# dennisquad.net
KiCad netlist of a schematic drawn in EAGLE
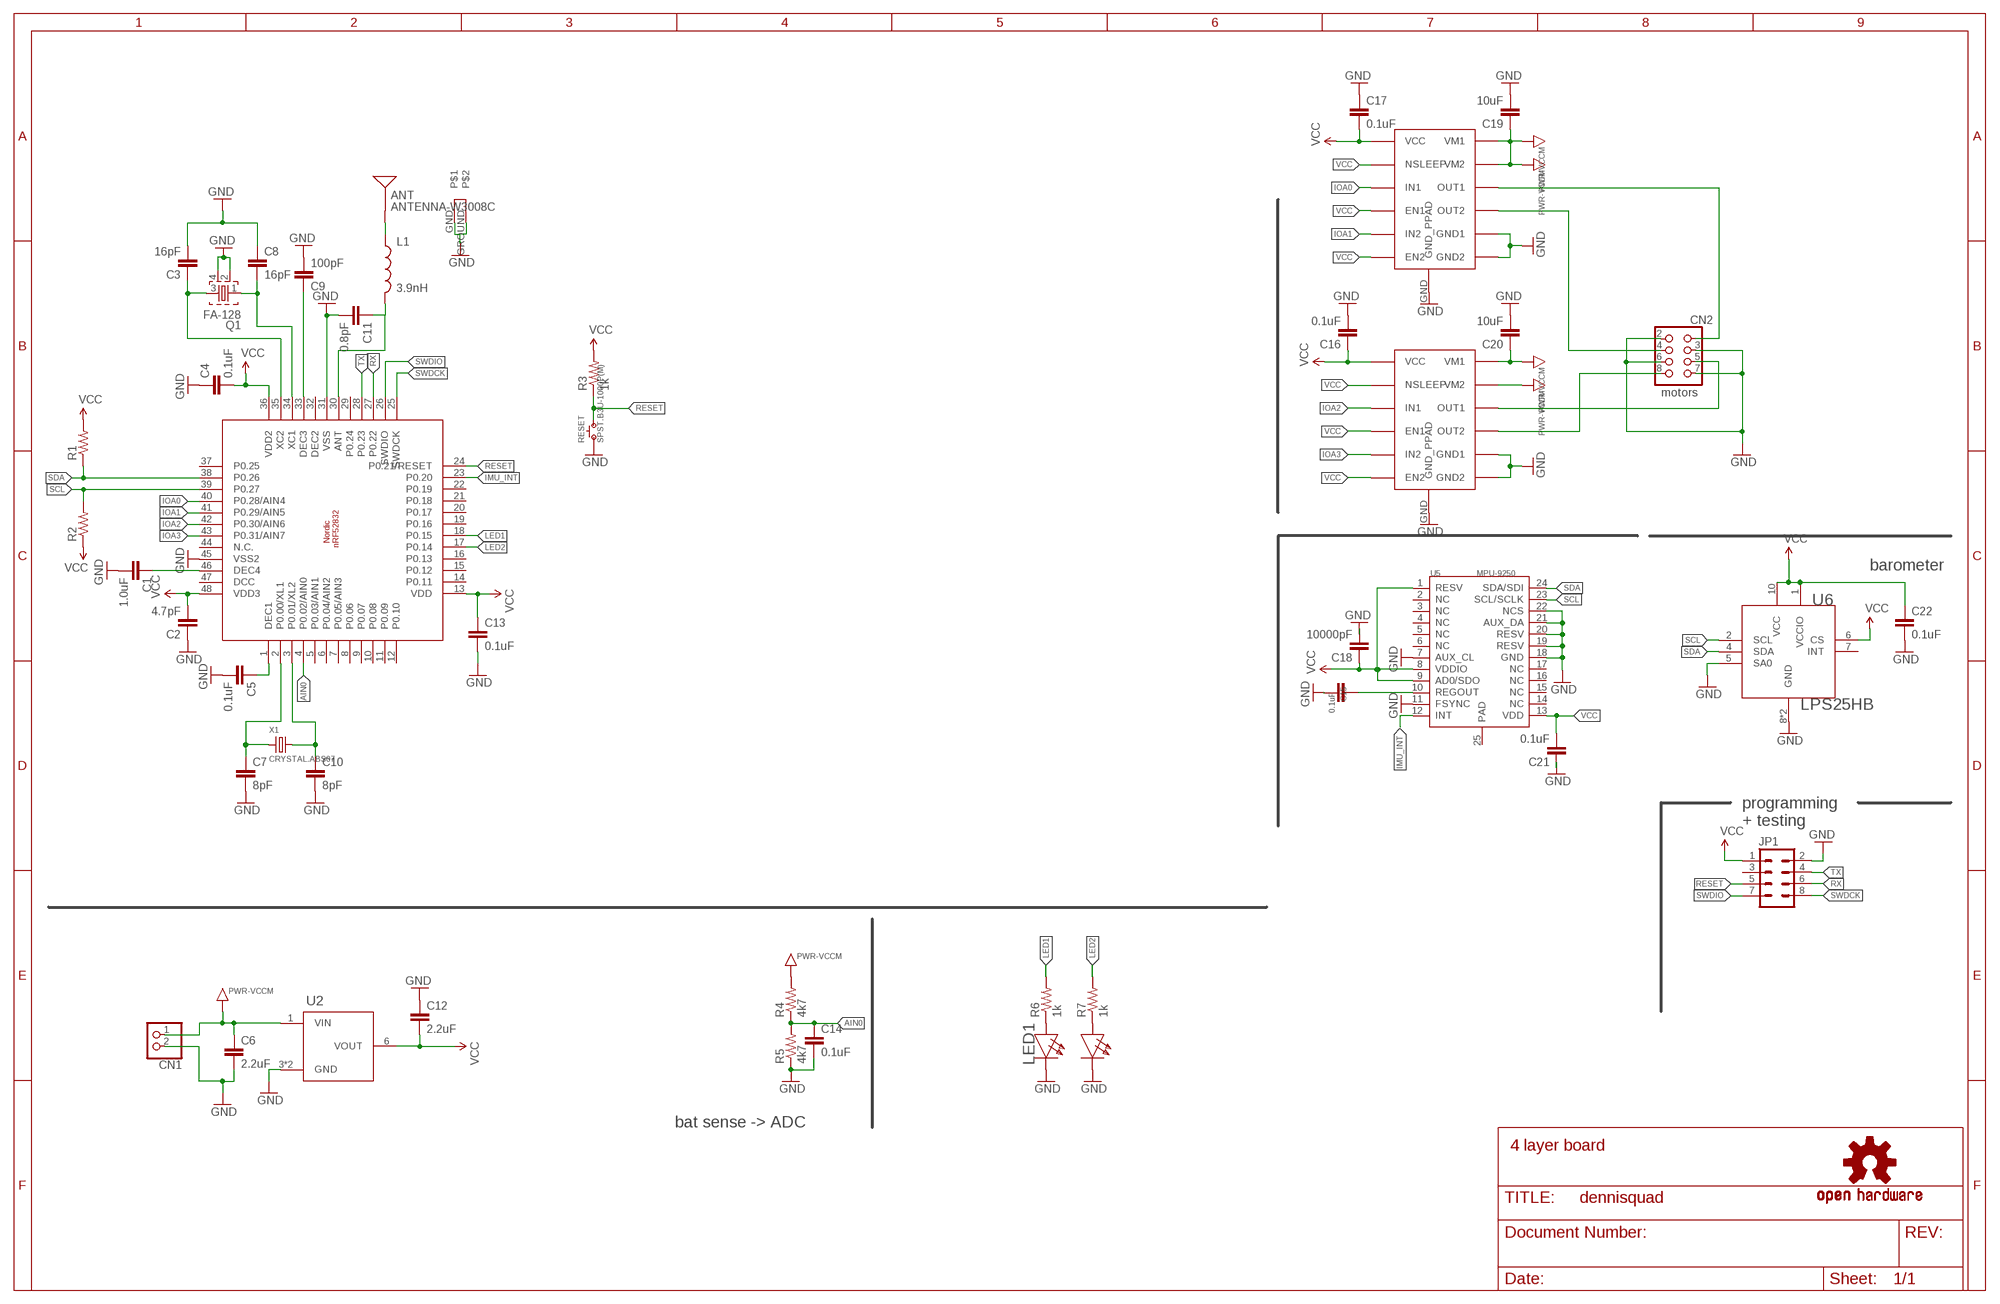
[diagram p0: schematic, sheet 1]

(export (version "E")
  (design (tool "Eeschema 10.0.6"))
  (components
    (comp (ref "ANT")
      (value "ANTENNA-W3008C")
      (footprint "eagle-import:ANTENNA-W3008C")
      (libsource (lib "eagle-import") (part "ANTENNA-W3008C"))
    )
    (comp (ref "C1")
      (value "1.0uF")
      (footprint "eagle-import:0603-CAP")
      (libsource (lib "eagle-import") (part "CAP0603-CAP"))
    )
    (comp (ref "C2")
      (value "4.7pF")
      (footprint "eagle-import:0603-CAP")
      (libsource (lib "eagle-import") (part "CAP0603-CAP"))
    )
    (comp (ref "C3")
      (value "16pF")
      (footprint "eagle-import:0402-CAP")
      (fields (field (name "MPN") "GRM1555C1H160GA01D"))
      (libsource (lib "eagle-import") (part "CAP0402-CAP"))
    )
    (comp (ref "C4")
      (value "0.1uF")
      (footprint "eagle-import:0402-CAP")
      (fields (field (name "MPN") "CL05B104JO5NNNC"))
      (libsource (lib "eagle-import") (part "CAP0402-CAP"))
    )
    (comp (ref "C5")
      (value "0.1uF")
      (footprint "eagle-import:0402-CAP")
      (fields (field (name "MPN") "CL05B104JO5NNNC"))
      (libsource (lib "eagle-import") (part "CAP0402-CAP"))
    )
    (comp (ref "C6")
      (value "2.2uF")
      (footprint "eagle-import:0402-CAP")
      (fields (field (name "MPN") "GRT155R61C225KE13D"))
      (libsource (lib "eagle-import") (part "CAP0402-CAP"))
    )
    (comp (ref "C7")
      (value "8pF")
      (footprint "eagle-import:0402-CAP")
      (fields (field (name "MPN") "GRM1555C1H8R0BA01D"))
      (libsource (lib "eagle-import") (part "CAP0402-CAP"))
    )
    (comp (ref "C8")
      (value "16pF")
      (footprint "eagle-import:0402-CAP")
      (fields (field (name "MPN") "GRM1555C1H160GA01D"))
      (libsource (lib "eagle-import") (part "CAP0402-CAP"))
    )
    (comp (ref "C9")
      (value "100pF")
      (footprint "eagle-import:0402-CAP")
      (fields (field (name "MPN") "GRM1555C1H101JA01D"))
      (libsource (lib "eagle-import") (part "CAP0402-CAP"))
    )
    (comp (ref "C10")
      (value "8pF")
      (footprint "eagle-import:0402-CAP")
      (fields (field (name "MPN") "GRM1555C1H8R0BA01D"))
      (libsource (lib "eagle-import") (part "CAP0402-CAP"))
    )
    (comp (ref "C11")
      (value "0.8pF")
      (footprint "eagle-import:0402-CAP")
      (fields (field (name "MPN") "GRM1555C2AR80BA01D"))
      (libsource (lib "eagle-import") (part "CAP0402-CAP"))
    )
    (comp (ref "C12")
      (value "2.2uF")
      (footprint "eagle-import:0402-CAP")
      (fields (field (name "MPN") "GRT155R61C225KE13D"))
      (libsource (lib "eagle-import") (part "CAP0402-CAP"))
    )
    (comp (ref "C13")
      (value "0.1uF")
      (footprint "eagle-import:0402-CAP")
      (fields (field (name "MPN") "CL05B104JO5NNNC"))
      (libsource (lib "eagle-import") (part "CAP0402-CAP"))
    )
    (comp (ref "C14")
      (value "0.1uF")
      (footprint "eagle-import:0402-CAP")
      (fields (field (name "MPN") "CL05B104JO5NNNC"))
      (libsource (lib "eagle-import") (part "CAP0402-CAP"))
    )
    (comp (ref "C15")
      (value "0.1uF")
      (footprint "eagle-import:0402-CAP")
      (fields (field (name "MPN") "CL05B104JO5NNNC"))
      (libsource (lib "eagle-import") (part "CAP0402-CAP"))
    )
    (comp (ref "C16")
      (value "0.1uF")
      (footprint "eagle-import:0402-CAP")
      (fields (field (name "MPN") "CL05B104JO5NNNC"))
      (libsource (lib "eagle-import") (part "CAP0402-CAP"))
    )
    (comp (ref "C17")
      (value "0.1uF")
      (footprint "eagle-import:0402-CAP")
      (fields (field (name "MPN") "CL05B104JO5NNNC"))
      (libsource (lib "eagle-import") (part "CAP0402-CAP"))
    )
    (comp (ref "C18")
      (value "10000pF")
      (footprint "eagle-import:0402-CAP")
      (fields (field (name "MPN") "CL05B103KP5NNNC"))
      (libsource (lib "eagle-import") (part "CAP0402-CAP"))
    )
    (comp (ref "C19")
      (value "10uF")
      (footprint "eagle-import:0603-CAP")
      (fields (field (name "MPN") "C1206C106M4RACAUTO"))
      (libsource (lib "eagle-import") (part "CAP0603-CAP"))
    )
    (comp (ref "C20")
      (value "10uF")
      (footprint "eagle-import:0603-CAP")
      (fields (field (name "MPN") "C1206C106M4RACAUTO"))
      (libsource (lib "eagle-import") (part "CAP0603-CAP"))
    )
    (comp (ref "C21")
      (value "0.1uF")
      (footprint "eagle-import:0402-CAP")
      (fields (field (name "MPN") "CL05B104JO5NNNC"))
      (libsource (lib "eagle-import") (part "CAP0402-CAP"))
    )
    (comp (ref "C22")
      (value "0.1uF")
      (footprint "eagle-import:0402-CAP")
      (fields (field (name "MPN") "CL05B104JO5NNNC"))
      (libsource (lib "eagle-import") (part "CAP0402-CAP"))
    )
    (comp (ref "CN1")
      (value "JST_2PIN-THM")
      (footprint "eagle-import:JST-PH-2-THM")
      (libsource (lib "eagle-import") (part "JST_2PIN-THM"))
    )
    (comp (ref "CN2")
      (value "HEADER-2X4")
      (footprint "eagle-import:HEADER-2X04-THM")
      (libsource (lib "eagle-import") (part "HEADER-2X4"))
    )
    (comp (ref "JP1")
      (value "M04X2")
      (footprint "eagle-import:2X4")
      (libsource (lib "eagle-import") (part "M04X2"))
    )
    (comp (ref "L1")
      (value "3.9nH")
      (footprint "eagle-import:0603")
      (fields (field (name "MPN") "AISC-0402-3N9J-T"))
      (libsource (lib "eagle-import") (part "INDUCTOR0603"))
    )
    (comp (ref "LED1")
      (value "LED-DUAL0805")
      (footprint "eagle-import:SMD0805-DUAL")
      (fields (field (name "MPN") "APHBM2012QBDSURKC"))
      (libsource (lib "eagle-import") (part "LED-DUAL0805"))
    )
    (comp (ref "LOGO1")
      (value "OSHW-LOGOM")
      (footprint "eagle-import:OSHW-LOGO-M")
      (libsource (lib "eagle-import") (part "OSHW-LOGOM"))
    )
    (comp (ref "Q1")
      (value "FA-128")
      (footprint "eagle-import:FA-128")
      (fields (field (name "MPN") "FA-128 32.0000MF20X-K3"))
      (libsource (lib "eagle-import") (part "FA-128"))
    )
    (comp (ref "R1")
      (value "RESISTOR0402")
      (footprint "eagle-import:0402-RES")
      (libsource (lib "eagle-import") (part "RESISTOR0402"))
    )
    (comp (ref "R2")
      (value "RESISTOR0402")
      (footprint "eagle-import:0402-RES")
      (libsource (lib "eagle-import") (part "RESISTOR0402"))
    )
    (comp (ref "R3")
      (value "1k")
      (footprint "eagle-import:0402-RES")
      (fields (field (name "MPN") "ERJ-2GEJ102X"))
      (libsource (lib "eagle-import") (part "RESISTOR0402"))
    )
    (comp (ref "R4")
      (value "4k7")
      (footprint "eagle-import:0402-RES")
      (fields (field (name "MPN") "ERJ-PA2F4701X"))
      (libsource (lib "eagle-import") (part "RESISTOR0402"))
    )
    (comp (ref "R5")
      (value "4k7")
      (footprint "eagle-import:0402-RES")
      (fields (field (name "MPN") "ERJ-PA2F4701X"))
      (libsource (lib "eagle-import") (part "RESISTOR0402"))
    )
    (comp (ref "R6")
      (value "1k")
      (footprint "eagle-import:0402-RES")
      (fields (field (name "MPN") "ERJ-2GEJ102X"))
      (libsource (lib "eagle-import") (part "RESISTOR0402"))
    )
    (comp (ref "R7")
      (value "1k")
      (footprint "eagle-import:0402-RES")
      (fields (field (name "MPN") "ERJ-2GEJ102X"))
      (libsource (lib "eagle-import") (part "RESISTOR0402"))
    )
    (comp (ref "RESET")
      (value "SPST.B3U-1000P(M)")
      (footprint "eagle-import:B3U-1000P(M)")
      (libsource (lib "eagle-import") (part "SPST.B3U-1000P(M)"))
    )
    (comp (ref "U1")
      (value "NRF52832_QFN48")
      (footprint "eagle-import:QFN48")
      (libsource (lib "eagle-import") (part "NRF52832_QFN48"))
    )
    (comp (ref "U2")
      (value "MCP1700T-3302E/MAY")
      (footprint "eagle-import:6-VDFN")
      (libsource (lib "eagle-import") (part "MCP1700T-3302E/MAY"))
    )
    (comp (ref "U3")
      (value "DRV8839")
      (footprint "eagle-import:PWSON-N12")
      (libsource (lib "eagle-import") (part "DRV8839"))
    )
    (comp (ref "U4")
      (value "DRV8839")
      (footprint "eagle-import:PWSON-N12")
      (libsource (lib "eagle-import") (part "DRV8839"))
    )
    (comp (ref "U5")
      (value "MPU-9250")
      (footprint "eagle-import:LEAD-QFN24")
      (libsource (lib "eagle-import") (part "MPU-9250"))
    )
    (comp (ref "U6")
      (value "LPS25HB")
      (footprint "eagle-import:HLGA10L")
      (libsource (lib "eagle-import") (part "LPS25HB"))
    )
    (comp (ref "X1")
      (value "CRYSTAL.ABS07")
      (footprint "eagle-import:ABS07")
      (fields (field (name "MPN") "ABS07-120-32.768KHZ-T"))
      (libsource (lib "eagle-import") (part "CRYSTAL.ABS07"))
    )
  )
  (nets
    (net (code "1") (name "/DCC") (class "Default")
      (node (ref "U1") (pin "47") (pinfunction "DCC_47") (pintype "power_in"))
    )
    (net (code "2") (name "/DEC2") (class "Default")
      (node (ref "U1") (pin "32") (pinfunction "DEC2_32") (pintype "power_in"))
    )
    (net (code "3") (name "AIN0") (class "Default")
      (node (ref "C14") (pin "1") (pinfunction "1_1") (pintype "passive"))
      (node (ref "R4") (pin "1") (pinfunction "1_1") (pintype "passive"))
      (node (ref "R5") (pin "2") (pinfunction "2_2") (pintype "passive"))
      (node (ref "U1") (pin "4") (pinfunction "P0.02/AIN0_4") (pintype "bidirectional"))
    )
    (net (code "4") (name "GND") (class "Default")
      (node (ref "ANT") (pin "GND") (pinfunction "P$1_GND") (pintype "bidirectional"))
      (node (ref "ANT") (pin "GROUND") (pinfunction "P$2_GROUND") (pintype "bidirectional"))
      (node (ref "C1") (pin "2") (pinfunction "2_2") (pintype "passive"))
      (node (ref "C10") (pin "2") (pinfunction "2_2") (pintype "passive"))
      (node (ref "C11") (pin "2") (pinfunction "2_2") (pintype "passive"))
      (node (ref "C12") (pin "1") (pinfunction "1_1") (pintype "passive"))
      (node (ref "C13") (pin "2") (pinfunction "2_2") (pintype "passive"))
      (node (ref "C14") (pin "2") (pinfunction "2_2") (pintype "passive"))
      (node (ref "C15") (pin "2") (pinfunction "2_2") (pintype "passive"))
      (node (ref "C16") (pin "2") (pinfunction "2_2") (pintype "passive"))
      (node (ref "C17") (pin "1") (pinfunction "1_1") (pintype "passive"))
      (node (ref "C18") (pin "2") (pinfunction "2_2") (pintype "passive"))
      (node (ref "C19") (pin "2") (pinfunction "2_2") (pintype "passive"))
      (node (ref "C2") (pin "1") (pinfunction "1_1") (pintype "passive"))
      (node (ref "C20") (pin "2") (pinfunction "2_2") (pintype "passive"))
      (node (ref "C21") (pin "1") (pinfunction "1_1") (pintype "passive"))
      (node (ref "C22") (pin "2") (pinfunction "2_2") (pintype "passive"))
      (node (ref "C3") (pin "2") (pinfunction "2_2") (pintype "passive"))
      (node (ref "C4") (pin "1") (pinfunction "1_1") (pintype "passive"))
      (node (ref "C5") (pin "2") (pinfunction "2_2") (pintype "passive"))
      (node (ref "C6") (pin "2") (pinfunction "2_2") (pintype "passive"))
      (node (ref "C7") (pin "2") (pinfunction "2_2") (pintype "passive"))
      (node (ref "C8") (pin "1") (pinfunction "1_1") (pintype "passive"))
      (node (ref "C9") (pin "2") (pinfunction "2_2") (pintype "passive"))
      (node (ref "CN1") (pin "2") (pinfunction "1_2") (pintype "passive"))
      (node (ref "CN2") (pin "2") (pinfunction "P$2_2") (pintype "passive"))
      (node (ref "CN2") (pin "3") (pinfunction "P$3_3") (pintype "passive"))
      (node (ref "CN2") (pin "6") (pinfunction "P$6_6") (pintype "passive"))
      (node (ref "CN2") (pin "7") (pinfunction "P$7_7") (pintype "passive"))
      (node (ref "JP1") (pin "2") (pinfunction "2_2") (pintype "passive"))
      (node (ref "LED1") (pin "2") (pinfunction "CB_2") (pintype "passive"))
      (node (ref "LED1") (pin "3") (pinfunction "CR_3") (pintype "passive"))
      (node (ref "Q1") (pin "2") (pinfunction "2_2") (pintype "passive"))
      (node (ref "Q1") (pin "4") (pinfunction "4_4") (pintype "passive"))
      (node (ref "R5") (pin "1") (pinfunction "1_1") (pintype "passive"))
      (node (ref "RESET") (pin "1") (pinfunction "1_1") (pintype "bidirectional"))
      (node (ref "U1") (pin "31") (pinfunction "VSS_31") (pintype "power_in"))
      (node (ref "U1") (pin "45") (pinfunction "VSS2_45") (pintype "power_in"))
      (node (ref "U2") (pin "3") (pinfunction "GND_3") (pintype "bidirectional"))
      (node (ref "U2") (pin "P$1") (pinfunction "GND_P$1") (pintype "bidirectional"))
      (node (ref "U3") (pin "GND") (pinfunction "GND_PPAD_GND") (pintype "bidirectional"))
      (node (ref "U3") (pin "P$5") (pinfunction "GND1_P$5") (pintype "bidirectional"))
      (node (ref "U3") (pin "P$6") (pinfunction "GND2_P$6") (pintype "bidirectional"))
      (node (ref "U4") (pin "GND") (pinfunction "GND_PPAD_GND") (pintype "bidirectional"))
      (node (ref "U4") (pin "P$5") (pinfunction "GND1_P$5") (pintype "bidirectional"))
      (node (ref "U4") (pin "P$6") (pinfunction "GND2_P$6") (pintype "bidirectional"))
      (node (ref "U5") (pin "11") (pinfunction "FSYNC_11") (pintype "bidirectional"))
      (node (ref "U5") (pin "18") (pinfunction "GND_18") (pintype "bidirectional"))
      (node (ref "U5") (pin "19") (pinfunction "RESV_19") (pintype "bidirectional"))
      (node (ref "U5") (pin "20") (pinfunction "RESV_20") (pintype "bidirectional"))
      (node (ref "U5") (pin "21") (pinfunction "AUX_DA_21") (pintype "bidirectional"))
      (node (ref "U5") (pin "22") (pinfunction "NCS_22") (pintype "bidirectional"))
      (node (ref "U5") (pin "7") (pinfunction "AUX_CL_7") (pintype "bidirectional"))
      (node (ref "U6") (pin "5") (pinfunction "SA0_5") (pintype "bidirectional"))
      (node (ref "U6") (pin "8") (pinfunction "GND_8") (pintype "bidirectional"))
      (node (ref "U6") (pin "9") (pinfunction "GND_9") (pintype "bidirectional"))
    )
    (net (code "5") (name "IMU_INT") (class "Default")
      (node (ref "U1") (pin "23") (pinfunction "P0.20_23") (pintype "bidirectional"))
      (node (ref "U5") (pin "12") (pinfunction "INT_12") (pintype "bidirectional"))
    )
    (net (code "6") (name "IOA0") (class "Default")
      (node (ref "U1") (pin "40") (pinfunction "P0.28/AIN4_40") (pintype "bidirectional"))
      (node (ref "U3") (pin "P$9") (pinfunction "IN1_P$9") (pintype "bidirectional"))
    )
    (net (code "7") (name "IOA1") (class "Default")
      (node (ref "U1") (pin "41") (pinfunction "P0.29/AIN5_41") (pintype "bidirectional"))
      (node (ref "U3") (pin "P$11") (pinfunction "IN2_P$11") (pintype "bidirectional"))
    )
    (net (code "8") (name "IOA2") (class "Default")
      (node (ref "U1") (pin "42") (pinfunction "P0.30/AIN6_42") (pintype "bidirectional"))
      (node (ref "U4") (pin "P$9") (pinfunction "IN1_P$9") (pintype "bidirectional"))
    )
    (net (code "9") (name "IOA3") (class "Default")
      (node (ref "U1") (pin "43") (pinfunction "P0.31/AIN7_43") (pintype "bidirectional"))
      (node (ref "U4") (pin "P$11") (pinfunction "IN2_P$11") (pintype "bidirectional"))
    )
    (net (code "10") (name "LED1") (class "Default")
      (node (ref "R6") (pin "2") (pinfunction "2_2") (pintype "passive"))
      (node (ref "U1") (pin "18") (pinfunction "P0.15_18") (pintype "bidirectional"))
    )
    (net (code "11") (name "LED2") (class "Default")
      (node (ref "R7") (pin "2") (pinfunction "2_2") (pintype "passive"))
      (node (ref "U1") (pin "17") (pinfunction "P0.14_17") (pintype "bidirectional"))
    )
    (net (code "12") (name "Net-(ANT-SIGNAL)") (class "Default")
      (node (ref "ANT") (pin "FEED") (pinfunction "SIGNAL_FEED") (pintype "bidirectional"))
      (node (ref "L1") (pin "1") (pinfunction "1_1") (pintype "passive"))
    )
    (net (code "13") (name "Net-(CN2-P$1)") (class "Default")
      (node (ref "CN2") (pin "1") (pinfunction "P$1_1") (pintype "passive"))
      (node (ref "U3") (pin "P$3") (pinfunction "OUT1_P$3") (pintype "bidirectional"))
    )
    (net (code "14") (name "Net-(CN2-P$4)") (class "Default")
      (node (ref "CN2") (pin "4") (pinfunction "P$4_4") (pintype "passive"))
      (node (ref "U3") (pin "P$4") (pinfunction "OUT2_P$4") (pintype "bidirectional"))
    )
    (net (code "15") (name "Net-(CN2-P$5)") (class "Default")
      (node (ref "CN2") (pin "5") (pinfunction "P$5_5") (pintype "passive"))
      (node (ref "U4") (pin "P$3") (pinfunction "OUT1_P$3") (pintype "bidirectional"))
    )
    (net (code "16") (name "Net-(CN2-P$8)") (class "Default")
      (node (ref "CN2") (pin "8") (pinfunction "P$8_8") (pintype "passive"))
      (node (ref "U4") (pin "P$4") (pinfunction "OUT2_P$4") (pintype "bidirectional"))
    )
    (net (code "17") (name "Net-(LED1-AB)") (class "Default")
      (node (ref "LED1") (pin "1") (pinfunction "AB_1") (pintype "passive"))
      (node (ref "R6") (pin "1") (pinfunction "1_1") (pintype "passive"))
    )
    (net (code "18") (name "Net-(LED1-AR)") (class "Default")
      (node (ref "LED1") (pin "4") (pinfunction "AR_4") (pintype "passive"))
      (node (ref "R7") (pin "1") (pinfunction "1_1") (pintype "passive"))
    )
    (net (code "19") (name "Net-(U1-ANT)") (class "Default")
      (node (ref "C11") (pin "1") (pinfunction "1_1") (pintype "passive"))
      (node (ref "L1") (pin "2") (pinfunction "2_2") (pintype "passive"))
      (node (ref "U1") (pin "30") (pinfunction "ANT_30") (pintype "bidirectional"))
    )
    (net (code "20") (name "Net-(U1-DEC1)") (class "Default")
      (node (ref "C5") (pin "1") (pinfunction "1_1") (pintype "passive"))
      (node (ref "U1") (pin "1") (pinfunction "DEC1_1") (pintype "power_in"))
    )
    (net (code "21") (name "Net-(U1-DEC3)") (class "Default")
      (node (ref "C9") (pin "1") (pinfunction "1_1") (pintype "passive"))
      (node (ref "U1") (pin "33") (pinfunction "DEC3_33") (pintype "power_in"))
    )
    (net (code "22") (name "Net-(U1-DEC4)") (class "Default")
      (node (ref "C1") (pin "1") (pinfunction "1_1") (pintype "passive"))
      (node (ref "U1") (pin "46") (pinfunction "DEC4_46") (pintype "bidirectional"))
    )
    (net (code "23") (name "Net-(U1-P0.00{slash}XL1)") (class "Default")
      (node (ref "C7") (pin "1") (pinfunction "1_1") (pintype "passive"))
      (node (ref "U1") (pin "2") (pinfunction "P0.00/XL1_2") (pintype "bidirectional"))
      (node (ref "X1") (pin "1") (pinfunction "1_1") (pintype "passive"))
    )
    (net (code "24") (name "Net-(U1-P0.01{slash}XL2)") (class "Default")
      (node (ref "C10") (pin "1") (pinfunction "1_1") (pintype "passive"))
      (node (ref "U1") (pin "3") (pinfunction "P0.01/XL2_3") (pintype "bidirectional"))
      (node (ref "X1") (pin "2") (pinfunction "2_2") (pintype "passive"))
    )
    (net (code "25") (name "Net-(U1-XC1)") (class "Default")
      (node (ref "C8") (pin "2") (pinfunction "2_2") (pintype "passive"))
      (node (ref "Q1") (pin "1") (pinfunction "1_1") (pintype "passive"))
      (node (ref "U1") (pin "34") (pinfunction "XC1_34") (pintype "bidirectional"))
    )
    (net (code "26") (name "Net-(U1-XC2)") (class "Default")
      (node (ref "C3") (pin "1") (pinfunction "1_1") (pintype "passive"))
      (node (ref "Q1") (pin "3") (pinfunction "3_3") (pintype "passive"))
      (node (ref "U1") (pin "35") (pinfunction "XC2_35") (pintype "bidirectional"))
    )
    (net (code "27") (name "Net-(U5-REGOUT)") (class "Default")
      (node (ref "C15") (pin "1") (pinfunction "1_1") (pintype "passive"))
      (node (ref "U5") (pin "10") (pinfunction "REGOUT_10") (pintype "bidirectional"))
    )
    (net (code "28") (name "PWR-VCCM") (class "Default")
      (node (ref "C19") (pin "1") (pinfunction "1_1") (pintype "passive"))
      (node (ref "C20") (pin "1") (pinfunction "1_1") (pintype "passive"))
      (node (ref "C6") (pin "1") (pinfunction "1_1") (pintype "passive"))
      (node (ref "CN1") (pin "1") (pinfunction "2_1") (pintype "passive"))
      (node (ref "R4") (pin "2") (pinfunction "2_2") (pintype "passive"))
      (node (ref "U2") (pin "1") (pinfunction "VIN_1") (pintype "bidirectional"))
      (node (ref "U3") (pin "P$1") (pinfunction "VM1_P$1") (pintype "bidirectional"))
      (node (ref "U3") (pin "P$2") (pinfunction "VM2_P$2") (pintype "bidirectional"))
      (node (ref "U4") (pin "P$1") (pinfunction "VM1_P$1") (pintype "bidirectional"))
      (node (ref "U4") (pin "P$2") (pinfunction "VM2_P$2") (pintype "bidirectional"))
    )
    (net (code "29") (name "RESET") (class "Default")
      (node (ref "JP1") (pin "5") (pinfunction "5_5") (pintype "passive"))
      (node (ref "R3") (pin "1") (pinfunction "1_1") (pintype "passive"))
      (node (ref "RESET") (pin "2") (pinfunction "2_2") (pintype "bidirectional"))
      (node (ref "U1") (pin "24") (pinfunction "P0.21/RESET_24") (pintype "bidirectional"))
    )
    (net (code "30") (name "RX") (class "Default")
      (node (ref "JP1") (pin "6") (pinfunction "6_6") (pintype "passive"))
      (node (ref "U1") (pin "27") (pinfunction "P0.22_27") (pintype "bidirectional"))
    )
    (net (code "31") (name "SCL") (class "Default")
      (node (ref "R2") (pin "2") (pinfunction "2_2") (pintype "passive"))
      (node (ref "U1") (pin "39") (pinfunction "P0.27_39") (pintype "bidirectional"))
      (node (ref "U5") (pin "23") (pinfunction "SCL/SCLK_23") (pintype "bidirectional"))
      (node (ref "U6") (pin "2") (pinfunction "SCL_2") (pintype "bidirectional"))
    )
    (net (code "32") (name "SDA") (class "Default")
      (node (ref "R1") (pin "1") (pinfunction "1_1") (pintype "passive"))
      (node (ref "U1") (pin "38") (pinfunction "P0.26_38") (pintype "bidirectional"))
      (node (ref "U5") (pin "24") (pinfunction "SDA/SDI_24") (pintype "bidirectional"))
      (node (ref "U6") (pin "4") (pinfunction "SDA_4") (pintype "bidirectional"))
    )
    (net (code "33") (name "SWDCK") (class "Default")
      (node (ref "JP1") (pin "8") (pinfunction "8_8") (pintype "passive"))
      (node (ref "U1") (pin "25") (pinfunction "SWDCK_25") (pintype "open_collector"))
    )
    (net (code "34") (name "SWDIO") (class "Default")
      (node (ref "JP1") (pin "7") (pinfunction "7_7") (pintype "passive"))
      (node (ref "U1") (pin "26") (pinfunction "SWDIO_26") (pintype "bidirectional"))
    )
    (net (code "35") (name "TX") (class "Default")
      (node (ref "JP1") (pin "4") (pinfunction "4_4") (pintype "passive"))
      (node (ref "U1") (pin "28") (pinfunction "P0.23_28") (pintype "bidirectional"))
    )
    (net (code "36") (name "VCC") (class "Default")
      (node (ref "C12") (pin "2") (pinfunction "2_2") (pintype "passive"))
      (node (ref "C13") (pin "1") (pinfunction "1_1") (pintype "passive"))
      (node (ref "C16") (pin "1") (pinfunction "1_1") (pintype "passive"))
      (node (ref "C17") (pin "2") (pinfunction "2_2") (pintype "passive"))
      (node (ref "C18") (pin "1") (pinfunction "1_1") (pintype "passive"))
      (node (ref "C2") (pin "2") (pinfunction "2_2") (pintype "passive"))
      (node (ref "C21") (pin "2") (pinfunction "2_2") (pintype "passive"))
      (node (ref "C22") (pin "1") (pinfunction "1_1") (pintype "passive"))
      (node (ref "C4") (pin "2") (pinfunction "2_2") (pintype "passive"))
      (node (ref "JP1") (pin "1") (pinfunction "1_1") (pintype "passive"))
      (node (ref "R1") (pin "2") (pinfunction "2_2") (pintype "passive"))
      (node (ref "R2") (pin "1") (pinfunction "1_1") (pintype "passive"))
      (node (ref "R3") (pin "2") (pinfunction "2_2") (pintype "passive"))
      (node (ref "U1") (pin "13") (pinfunction "VDD_13") (pintype "power_in"))
      (node (ref "U1") (pin "36") (pinfunction "VDD2_36") (pintype "power_in"))
      (node (ref "U1") (pin "48") (pinfunction "VDD3_48") (pintype "power_in"))
      (node (ref "U2") (pin "6") (pinfunction "VOUT_6") (pintype "bidirectional"))
      (node (ref "U3") (pin "P$10") (pinfunction "EN1_P$10") (pintype "bidirectional"))
      (node (ref "U3") (pin "P$12") (pinfunction "EN2_P$12") (pintype "bidirectional"))
      (node (ref "U3") (pin "P$7") (pinfunction "VCC_P$7") (pintype "bidirectional"))
      (node (ref "U3") (pin "P$8") (pinfunction "NSLEEP_P$8") (pintype "bidirectional"))
      (node (ref "U4") (pin "P$10") (pinfunction "EN1_P$10") (pintype "bidirectional"))
      (node (ref "U4") (pin "P$12") (pinfunction "EN2_P$12") (pintype "bidirectional"))
      (node (ref "U4") (pin "P$7") (pinfunction "VCC_P$7") (pintype "bidirectional"))
      (node (ref "U4") (pin "P$8") (pinfunction "NSLEEP_P$8") (pintype "bidirectional"))
      (node (ref "U5") (pin "1") (pinfunction "RESV_1") (pintype "bidirectional"))
      (node (ref "U5") (pin "13") (pinfunction "VDD_13") (pintype "bidirectional"))
      (node (ref "U5") (pin "8") (pinfunction "VDDIO_8") (pintype "bidirectional"))
      (node (ref "U5") (pin "9") (pinfunction "AD0/SDO_9") (pintype "bidirectional"))
      (node (ref "U6") (pin "1") (pinfunction "VCCIO_1") (pintype "bidirectional"))
      (node (ref "U6") (pin "10") (pinfunction "VCC_10") (pintype "bidirectional"))
      (node (ref "U6") (pin "6") (pinfunction "CS_6") (pintype "bidirectional"))
    )
    (net (code "37") (name "unconnected-(JP1-Pad3)") (class "Default")
      (node (ref "JP1") (pin "3") (pinfunction "3_3") (pintype "passive"))
    )
    (net (code "38") (name "unconnected-(U1-N.C.-Pad44)") (class "Default")
      (node (ref "U1") (pin "44") (pinfunction "N.C._44") (pintype "no_connect"))
    )
    (net (code "39") (name "unconnected-(U1-P0.03{slash}AIN1-Pad5)") (class "Default")
      (node (ref "U1") (pin "5") (pinfunction "P0.03/AIN1_5") (pintype "bidirectional"))
    )
    (net (code "40") (name "unconnected-(U1-P0.04{slash}AIN2-Pad6)") (class "Default")
      (node (ref "U1") (pin "6") (pinfunction "P0.04/AIN2_6") (pintype "bidirectional"))
    )
    (net (code "41") (name "unconnected-(U1-P0.05{slash}AIN3-Pad7)") (class "Default")
      (node (ref "U1") (pin "7") (pinfunction "P0.05/AIN3_7") (pintype "bidirectional"))
    )
    (net (code "42") (name "unconnected-(U1-P0.06-Pad8)") (class "Default")
      (node (ref "U1") (pin "8") (pinfunction "P0.06_8") (pintype "bidirectional"))
    )
    (net (code "43") (name "unconnected-(U1-P0.07-Pad9)") (class "Default")
      (node (ref "U1") (pin "9") (pinfunction "P0.07_9") (pintype "bidirectional"))
    )
    (net (code "44") (name "unconnected-(U1-P0.08-Pad10)") (class "Default")
      (node (ref "U1") (pin "10") (pinfunction "P0.08_10") (pintype "bidirectional"))
    )
    (net (code "45") (name "unconnected-(U1-P0.09-Pad11)") (class "Default")
      (node (ref "U1") (pin "11") (pinfunction "P0.09_11") (pintype "bidirectional"))
    )
    (net (code "46") (name "unconnected-(U1-P0.10-Pad12)") (class "Default")
      (node (ref "U1") (pin "12") (pinfunction "P0.10_12") (pintype "bidirectional"))
    )
    (net (code "47") (name "unconnected-(U1-P0.11-Pad14)") (class "Default")
      (node (ref "U1") (pin "14") (pinfunction "P0.11_14") (pintype "bidirectional"))
    )
    (net (code "48") (name "unconnected-(U1-P0.12-Pad15)") (class "Default")
      (node (ref "U1") (pin "15") (pinfunction "P0.12_15") (pintype "bidirectional"))
    )
    (net (code "49") (name "unconnected-(U1-P0.13-Pad16)") (class "Default")
      (node (ref "U1") (pin "16") (pinfunction "P0.13_16") (pintype "bidirectional"))
    )
    (net (code "50") (name "unconnected-(U1-P0.16-Pad19)") (class "Default")
      (node (ref "U1") (pin "19") (pinfunction "P0.16_19") (pintype "bidirectional"))
    )
    (net (code "51") (name "unconnected-(U1-P0.17-Pad20)") (class "Default")
      (node (ref "U1") (pin "20") (pinfunction "P0.17_20") (pintype "bidirectional"))
    )
    (net (code "52") (name "unconnected-(U1-P0.18-Pad21)") (class "Default")
      (node (ref "U1") (pin "21") (pinfunction "P0.18_21") (pintype "bidirectional"))
    )
    (net (code "53") (name "unconnected-(U1-P0.19-Pad22)") (class "Default")
      (node (ref "U1") (pin "22") (pinfunction "P0.19_22") (pintype "bidirectional"))
    )
    (net (code "54") (name "unconnected-(U1-P0.24-Pad29)") (class "Default")
      (node (ref "U1") (pin "29") (pinfunction "P0.24_29") (pintype "bidirectional"))
    )
    (net (code "55") (name "unconnected-(U1-P0.25-Pad37)") (class "Default")
      (node (ref "U1") (pin "37") (pinfunction "P0.25_37") (pintype "bidirectional"))
    )
    (net (code "56") (name "unconnected-(U5-NC-Pad2)") (class "Default")
      (node (ref "U5") (pin "2") (pinfunction "NC_2") (pintype "bidirectional"))
    )
    (net (code "57") (name "unconnected-(U5-NC-Pad3)") (class "Default")
      (node (ref "U5") (pin "3") (pinfunction "NC_3") (pintype "bidirectional"))
    )
    (net (code "58") (name "unconnected-(U5-NC-Pad4)") (class "Default")
      (node (ref "U5") (pin "4") (pinfunction "NC_4") (pintype "bidirectional"))
    )
    (net (code "59") (name "unconnected-(U5-NC-Pad5)") (class "Default")
      (node (ref "U5") (pin "5") (pinfunction "NC_5") (pintype "bidirectional"))
    )
    (net (code "60") (name "unconnected-(U5-NC-Pad6)") (class "Default")
      (node (ref "U5") (pin "6") (pinfunction "NC_6") (pintype "bidirectional"))
    )
    (net (code "61") (name "unconnected-(U5-NC-Pad14)") (class "Default")
      (node (ref "U5") (pin "14") (pinfunction "NC_14") (pintype "bidirectional"))
    )
    (net (code "62") (name "unconnected-(U5-NC-Pad15)") (class "Default")
      (node (ref "U5") (pin "15") (pinfunction "NC_15") (pintype "bidirectional"))
    )
    (net (code "63") (name "unconnected-(U5-NC-Pad16)") (class "Default")
      (node (ref "U5") (pin "16") (pinfunction "NC_16") (pintype "bidirectional"))
    )
    (net (code "64") (name "unconnected-(U5-NC-Pad17)") (class "Default")
      (node (ref "U5") (pin "17") (pinfunction "NC_17") (pintype "bidirectional"))
    )
    (net (code "65") (name "unconnected-(U5-PAD-Pad25)") (class "Default")
      (node (ref "U5") (pin "25") (pinfunction "PAD_25") (pintype "bidirectional"))
    )
    (net (code "66") (name "unconnected-(U6-INT-Pad7)") (class "Default")
      (node (ref "U6") (pin "7") (pinfunction "INT_7") (pintype "bidirectional"))
    )
  )
)
